# PIC18F14K50.net
KiCad netlist of a schematic drawn in Altium Designer
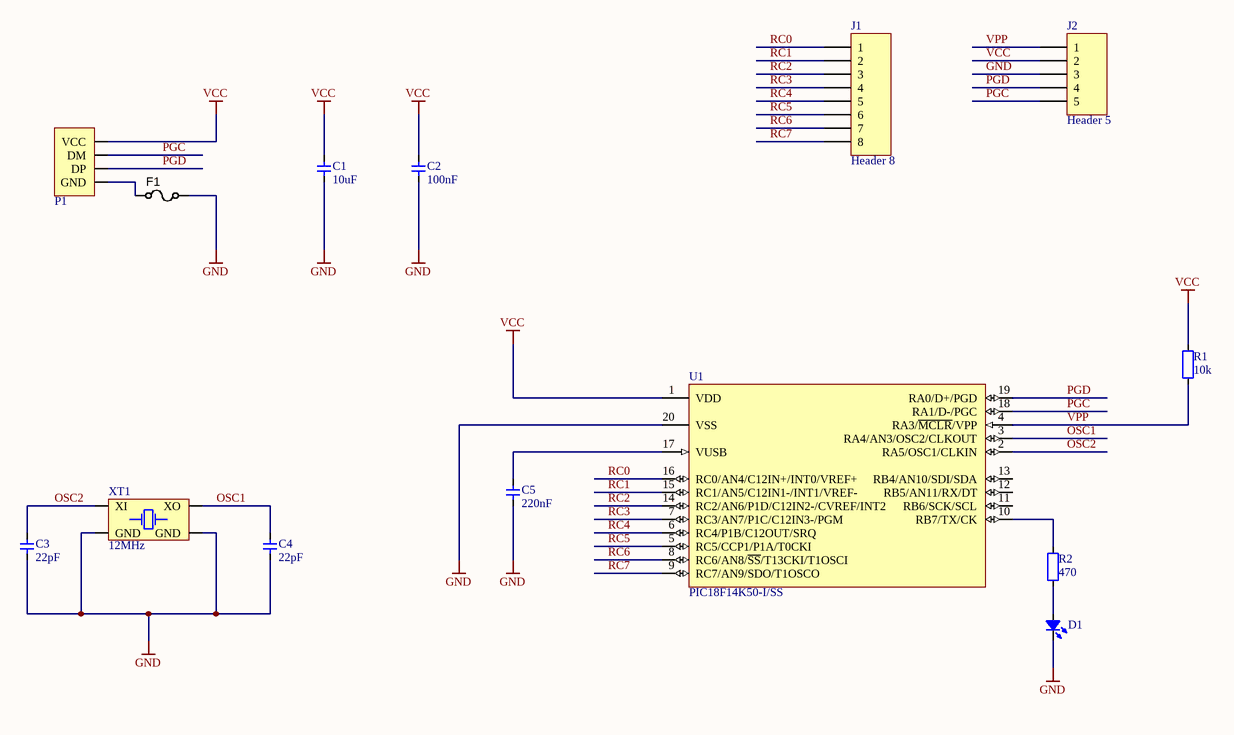
[diagram p0: PIC18F14K50.SchDoc]

(export (version "E")
  (design (tool "Eeschema 10.0.6"))
  (components
    (comp (ref "C1")
      (value "10uF")
      (footprint "PCB_PassiveCap:CAP_0603")
      (description "Capacitor")
      (fields (field (name "Comment") "Cap_0603"))
      (libsource (lib "SCH_Passive") (part "Cap_0603"))
    )
    (comp (ref "C2")
      (value "100nF")
      (footprint "PCB_PassiveCap:CAP_0603")
      (description "Capacitor")
      (fields (field (name "Comment") "Cap_0603"))
      (libsource (lib "SCH_Passive") (part "Cap_0603"))
    )
    (comp (ref "C3")
      (value "22pF")
      (footprint "PCB_PassiveCap:CAP_0603")
      (description "Capacitor")
      (fields (field (name "Comment") "Cap_0603"))
      (libsource (lib "SCH_Passive") (part "Cap_0603"))
    )
    (comp (ref "C4")
      (value "22pF")
      (footprint "PCB_PassiveCap:CAP_0603")
      (description "Capacitor")
      (fields (field (name "Comment") "Cap_0603"))
      (libsource (lib "SCH_Passive") (part "Cap_0603"))
    )
    (comp (ref "C5")
      (value "220nF")
      (footprint "PCB_PassiveCap:CAP_0603")
      (description "Capacitor")
      (fields (field (name "Comment") "Cap_0603"))
      (libsource (lib "SCH_Passive") (part "Cap_0603"))
    )
    (comp (ref "D1")
      (value "LED_0603")
      (footprint "PCB_ActiveLED:LED_0603_RED")
      (description "LED")
      (libsource (lib "SCH_Active") (part "LED_0603"))
    )
    (comp (ref "F1")
      (value "Slow-blow")
      (footprint "RESC3216X70N")
      (description "Fuse 750mA 6VDC 1206 SMD")
      (libsource (lib "PBL - Fuses and Protection") (part "FUSE_160mA_1206"))
    )
    (comp (ref "J1")
      (value "Header 8")
      (footprint "HDR1X8")
      (description "Header, 8-Pin")
      (fields (field (name "PUBLISHER") "Altium Limited"))
      (libsource (lib "Miscellaneous Connectors") (part "Header 8"))
    )
    (comp (ref "J2")
      (value "Header 5")
      (footprint "HDR1X5")
      (description "Header, 5-Pin")
      (fields (field (name "PUBLISHER") "Altium Limited"))
      (libsource (lib "Miscellaneous Connectors") (part "Header 5"))
    )
    (comp (ref "P1")
      (value "USB_Plug_TypeA")
      (footprint "PCB_USB:USB_Plug_TypeA")
      (description "USB")
      (libsource (lib "SCH_USB") (part "USB_Plug_TypeA"))
    )
    (comp (ref "R1")
      (value "10k")
      (footprint "PCB_PassiveRes:RES_0603")
      (description "Resistor")
      (fields (field (name "Comment") "Res_0603"))
      (libsource (lib "SCH_Passive") (part "Res_0603"))
    )
    (comp (ref "R2")
      (value "470")
      (footprint "PCB_PassiveRes:RES_0603")
      (description "Resistor")
      (fields (field (name "Comment") "Res_0603"))
      (libsource (lib "SCH_Passive") (part "Res_0603"))
    )
    (comp (ref "U1")
      (value "PIC18F14K50-I/SS")
      (footprint "SSOP-SS20_N")
      (description "USB Flash Microcontroller with nanoWatt XLP Technology, 20-pin SSOP, Industrial Temperature")
      (fields (field (name "PUBLISHER") "Altium Limited"))
      (libsource (lib "Microchip Microcontroller 8-Bit PIC18") (part "PIC18F14K50-I/SS"))
    )
    (comp (ref "XT1")
      (value "12MHz")
      (footprint "PCB_Oscillator:XT_2520_4")
      (description "Crystal Oscillator")
      (fields (field (name "Comment") "XTAL_2520_4P"))
      (libsource (lib "SCH_Oscillator") (part "XTAL_2520_4P"))
    )
  )
  (nets
    (net (code "1") (name "/OSC1") (class "Default")
      (node (ref "C4") (pin "2") (pinfunction "2_2") (pintype "passive"))
      (node (ref "U1") (pin "3") (pinfunction "RA4/AN3/OSC2/CLKOUT_3") (pintype "bidirectional"))
      (node (ref "XT1") (pin "3") (pinfunction "XO_3") (pintype "passive"))
    )
    (net (code "2") (name "/OSC2") (class "Default")
      (node (ref "C3") (pin "2") (pinfunction "2_2") (pintype "passive"))
      (node (ref "U1") (pin "2") (pinfunction "RA5/OSC1/CLKIN_2") (pintype "bidirectional"))
      (node (ref "XT1") (pin "1") (pinfunction "XI_1") (pintype "passive"))
    )
    (net (code "3") (name "/PGC") (class "Default")
      (node (ref "J2") (pin "5") (pinfunction "5_5") (pintype "passive"))
      (node (ref "P1") (pin "2") (pinfunction "DM_2") (pintype "passive"))
      (node (ref "U1") (pin "18") (pinfunction "RA1/D-/PGC_18") (pintype "bidirectional"))
    )
    (net (code "4") (name "/PGD") (class "Default")
      (node (ref "J2") (pin "4") (pinfunction "4_4") (pintype "passive"))
      (node (ref "P1") (pin "3") (pinfunction "DP_3") (pintype "passive"))
      (node (ref "U1") (pin "19") (pinfunction "RA0/D+/PGD_19") (pintype "bidirectional"))
    )
    (net (code "5") (name "/RC0") (class "Default")
      (node (ref "J1") (pin "1") (pinfunction "1_1") (pintype "passive"))
      (node (ref "U1") (pin "16") (pinfunction "RC0/AN4/C12IN+/INT0/VREF+_16") (pintype "bidirectional"))
    )
    (net (code "6") (name "/RC1") (class "Default")
      (node (ref "J1") (pin "2") (pinfunction "2_2") (pintype "passive"))
      (node (ref "U1") (pin "15") (pinfunction "RC1/AN5/C12IN1-/INT1/VREF-_15") (pintype "bidirectional"))
    )
    (net (code "7") (name "/RC2") (class "Default")
      (node (ref "J1") (pin "3") (pinfunction "3_3") (pintype "passive"))
      (node (ref "U1") (pin "14") (pinfunction "RC2/AN6/P1D/C12IN2-/CVREF/INT2_14") (pintype "bidirectional"))
    )
    (net (code "8") (name "/RC3") (class "Default")
      (node (ref "J1") (pin "4") (pinfunction "4_4") (pintype "passive"))
      (node (ref "U1") (pin "7") (pinfunction "RC3/AN7/P1C/C12IN3-/PGM_7") (pintype "bidirectional"))
    )
    (net (code "9") (name "/RC4") (class "Default")
      (node (ref "J1") (pin "5") (pinfunction "5_5") (pintype "passive"))
      (node (ref "U1") (pin "6") (pinfunction "RC4/P1B/C12OUT/SRQ_6") (pintype "bidirectional"))
    )
    (net (code "10") (name "/RC5") (class "Default")
      (node (ref "J1") (pin "6") (pinfunction "6_6") (pintype "passive"))
      (node (ref "U1") (pin "5") (pinfunction "RC5/CCP1/P1A/T0CKI_5") (pintype "bidirectional"))
    )
    (net (code "11") (name "/RC6") (class "Default")
      (node (ref "J1") (pin "7") (pinfunction "7_7") (pintype "passive"))
      (node (ref "U1") (pin "8") (pinfunction "RC6/AN8/~{SS}/T13CKI/T1OSCI_8") (pintype "bidirectional"))
    )
    (net (code "12") (name "/RC7") (class "Default")
      (node (ref "J1") (pin "8") (pinfunction "8_8") (pintype "passive"))
      (node (ref "U1") (pin "9") (pinfunction "RC7/AN9/SDO/T1OSCO_9") (pintype "bidirectional"))
    )
    (net (code "13") (name "/VPP") (class "Default")
      (node (ref "J2") (pin "1") (pinfunction "1_1") (pintype "passive"))
      (node (ref "R1") (pin "1") (pinfunction "1_1") (pintype "passive"))
      (node (ref "U1") (pin "4") (pinfunction "RA3/~{MCLR}/VPP_4") (pintype "input"))
    )
    (net (code "14") (name "GND") (class "Default")
      (node (ref "C1") (pin "1") (pinfunction "1_1") (pintype "passive"))
      (node (ref "C2") (pin "1") (pinfunction "1_1") (pintype "passive"))
      (node (ref "C3") (pin "1") (pinfunction "1_1") (pintype "passive"))
      (node (ref "C4") (pin "1") (pinfunction "1_1") (pintype "passive"))
      (node (ref "C5") (pin "1") (pinfunction "1_1") (pintype "passive"))
      (node (ref "D1") (pin "2") (pinfunction "K_2") (pintype "passive"))
      (node (ref "F1") (pin "2") (pinfunction "2_2") (pintype "passive"))
      (node (ref "J2") (pin "3") (pinfunction "3_3") (pintype "passive"))
      (node (ref "U1") (pin "20") (pinfunction "VSS_20") (pintype "power_in"))
      (node (ref "XT1") (pin "2") (pinfunction "GND_2") (pintype "passive"))
      (node (ref "XT1") (pin "4") (pinfunction "GND_4") (pintype "passive"))
    )
    (net (code "15") (name "Net-(D1-A)") (class "Default")
      (node (ref "D1") (pin "1") (pinfunction "A_1") (pintype "passive"))
      (node (ref "R2") (pin "1") (pinfunction "1_1") (pintype "passive"))
    )
    (net (code "16") (name "Net-(P1-GND)") (class "Default")
      (node (ref "F1") (pin "1") (pinfunction "1_1") (pintype "passive"))
      (node (ref "P1") (pin "4") (pinfunction "GND_4") (pintype "passive"))
    )
    (net (code "17") (name "Net-(U1-RB7{slash}TX{slash}CK)") (class "Default")
      (node (ref "R2") (pin "2") (pinfunction "2_2") (pintype "passive"))
      (node (ref "U1") (pin "10") (pinfunction "RB7/TX/CK_10") (pintype "bidirectional"))
    )
    (net (code "18") (name "Net-(U1-VUSB)") (class "Default")
      (node (ref "C5") (pin "2") (pinfunction "2_2") (pintype "passive"))
      (node (ref "U1") (pin "17") (pinfunction "VUSB_17") (pintype "input"))
    )
    (net (code "19") (name "VCC") (class "Default")
      (node (ref "C1") (pin "2") (pinfunction "2_2") (pintype "passive"))
      (node (ref "C2") (pin "2") (pinfunction "2_2") (pintype "passive"))
      (node (ref "J2") (pin "2") (pinfunction "2_2") (pintype "passive"))
      (node (ref "P1") (pin "1") (pinfunction "VCC_1") (pintype "passive"))
      (node (ref "R1") (pin "2") (pinfunction "2_2") (pintype "passive"))
      (node (ref "U1") (pin "1") (pinfunction "VDD_1") (pintype "power_in"))
    )
    (net (code "20") (name "unconnected-(U1-RB4{slash}AN10{slash}SDI{slash}SDA-Pad13)") (class "Default")
      (node (ref "U1") (pin "13") (pinfunction "RB4/AN10/SDI/SDA_13") (pintype "bidirectional"))
    )
    (net (code "21") (name "unconnected-(U1-RB5{slash}AN11{slash}RX{slash}DT-Pad12)") (class "Default")
      (node (ref "U1") (pin "12") (pinfunction "RB5/AN11/RX/DT_12") (pintype "bidirectional"))
    )
    (net (code "22") (name "unconnected-(U1-RB6{slash}SCK{slash}SCL-Pad11)") (class "Default")
      (node (ref "U1") (pin "11") (pinfunction "RB6/SCK/SCL_11") (pintype "bidirectional"))
    )
  )
)
